# 78M05_RT9193.net
KiCad netlist of a schematic drawn in Altium Designer
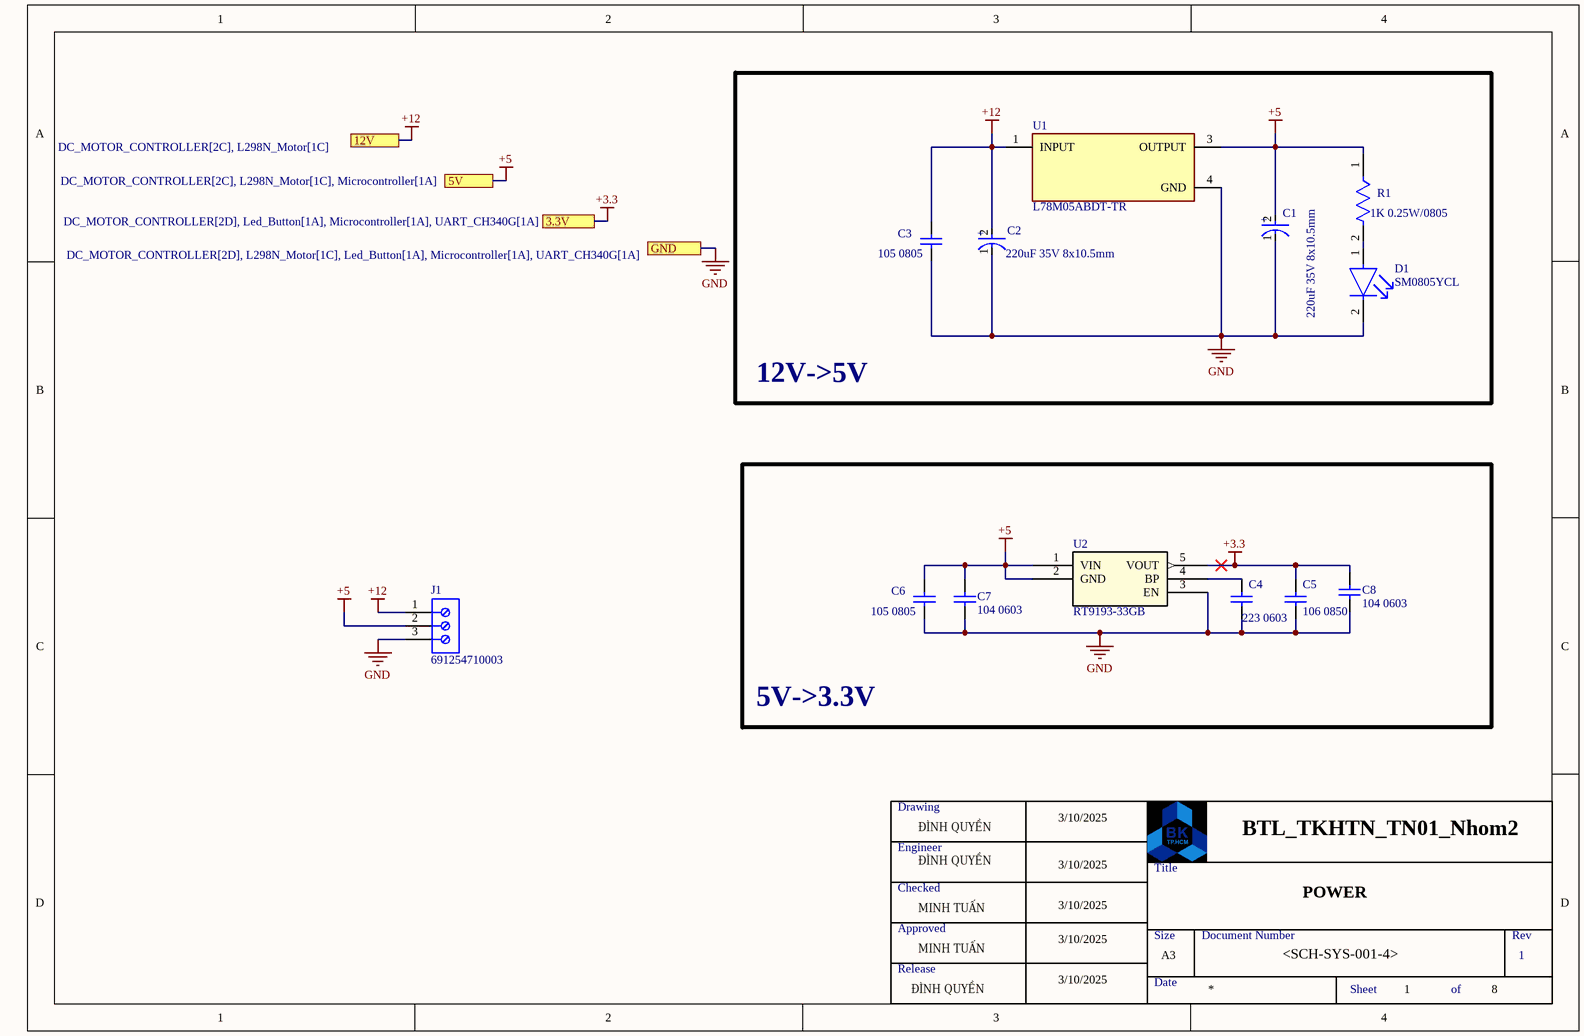
[diagram p0: 78M05_RT9193.SchDoc]

(export (version "E")
  (design (tool "Eeschema 10.0.6"))
  (components
    (comp (ref "C1")
      (value "220uF 35V 8x10.5mm")
      (footprint "FP-FPF-MFG")
      (description "CAP ALUM 220UF 20% 35V SMD")
      (fields (field (name "TOLERANCE") "20%") (field (name "VOLTAGE") "35V"))
      (libsource (lib "Altium Content Vault") (part "203bc49f2ac43e59fd269a8c329ed05"))
    )
    (comp (ref "C2")
      (value "220uF 35V 8x10.5mm")
      (footprint "FP-FPF-MFG")
      (description "CAP ALUM 220UF 20% 35V SMD")
      (fields (field (name "TOLERANCE") "20%") (field (name "VOLTAGE") "35V"))
      (libsource (lib "Altium Content Vault") (part "203bc49f2ac43e59fd269a8c329ed05"))
    )
    (comp (ref "C3")
      (value "105 0805")
      (footprint "CAPC0805(2012)145_M")
      (description "CAP 15nF 100V ±10% 0805 (2012 Metric) Thickness 1.45mm SMD")
      (fields (field (name "TOLERANCE") "Â±10%"))
      (libsource (lib "Altium Content Vault") (part "CAP"))
    )
    (comp (ref "C4")
      (value "223 0603")
      (footprint "CAPC1608X92X38ML15T08")
      (fields (field (name "MANUFACTURER") "Vitramon") (field (name "PART NUMBER") "VJ0603Y103JXXAC"))
      (libsource (lib "Altium Content Vault") (part "CAP"))
    )
    (comp (ref "C5")
      (value "106 0850")
      (footprint "CAPC0805(2012)145_M")
      (description "CAP 15nF 100V ±10% 0805 (2012 Metric) Thickness 1.45mm SMD")
      (fields (field (name "TOLERANCE") "Â±10%"))
      (libsource (lib "Altium Content Vault") (part "CAP"))
    )
    (comp (ref "C6")
      (value "105 0805")
      (footprint "CAPC0805(2012)145_M")
      (description "CAP 15nF 100V ±10% 0805 (2012 Metric) Thickness 1.45mm SMD")
      (fields (field (name "TOLERANCE") "Â±10%"))
      (libsource (lib "Altium Content Vault") (part "CAP"))
    )
    (comp (ref "C7")
      (value "104 0603")
      (footprint "CAPC1608X92X38ML15T08")
      (fields (field (name "MANUFACTURER") "Vitramon") (field (name "PART NUMBER") "VJ0603Y103JXXAC"))
      (libsource (lib "Altium Content Vault") (part "CAP"))
    )
    (comp (ref "C8")
      (value "104 0603")
      (footprint "CAPC1608X92X38ML15T08")
      (fields (field (name "MANUFACTURER") "Vitramon") (field (name "PART NUMBER") "VJ0603Y103JXXAC"))
      (libsource (lib "Altium Content Vault") (part "CAP"))
    )
    (comp (ref "D1")
      (value "SM0805YCL")
      (footprint "FP-SM0805YCL-MFG")
      (description "LED YELLOW CLEAR 0805 SMD")
      (libsource (lib "Altium Content Vault") (part "ab1c01a81903e929fc6c44469aada92"))
    )
    (comp (ref "J1")
      (value "691254710003")
      (footprint "691254710003")
      (libsource (lib "Altium Content Vault") (part "TBL - 1R - 03P - Screw"))
    )
    (comp (ref "R1")
      (value "1K 0.25W/0805")
      (footprint "FP-AF0805-IPC_C")
      (description "Anti-Sulfurated Chip Resistor Automotive Grade 75Ω 1% 0.125W ±100ppm/°C 0805")
      (fields (field (name "TOLERANCE") "1%"))
      (libsource (lib "Altium Content Vault") (part "1029c3af85768c4190bb7ad29bc67b5"))
    )
    (comp (ref "U1")
      (value "L78M05ABDT-TR")
      (footprint "FP-L78M05ABDT-TR-MFG")
      (description "IC REG LINEAR 5V 500MA DPAK")
      (fields (field (name "TOLERANCE") "4%"))
      (libsource (lib "Altium Content Vault") (part "9f44cecb34f7d82ec50de3d0489c717"))
    )
    (comp (ref "U2")
      (value "RT9193-33GB")
      (footprint "SOT-23-5_RIT")
      (description "No Description Available")
      (fields (field (name "COPYRIGHT") "Copyright (C) 2025 Ultra Librarian. All rights reserved."))
      (libsource (lib "RT9193-33GB") (part "RT9193-33GB"))
    )
  )
  (nets
    (net (code "1") (name "+3.3") (class "Default")
      (node (ref "C5") (pin "2") (pinfunction "2_2") (pintype "passive"))
      (node (ref "C8") (pin "2") (pinfunction "2_2") (pintype "passive"))
      (node (ref "U2") (pin "5") (pinfunction "VOUT_5") (pintype "output"))
    )
    (net (code "2") (name "+5") (class "Default")
      (node (ref "C1") (pin "2") (pinfunction "A_2") (pintype "passive"))
      (node (ref "C6") (pin "2") (pinfunction "2_2") (pintype "passive"))
      (node (ref "C7") (pin "2") (pinfunction "2_2") (pintype "passive"))
      (node (ref "J1") (pin "2") (pinfunction "2_2") (pintype "passive"))
      (node (ref "R1") (pin "1") (pinfunction "1_1") (pintype "passive"))
      (node (ref "U1") (pin "3") (pinfunction "OUTPUT_3") (pintype "power_in"))
      (node (ref "U2") (pin "1") (pinfunction "VIN_1") (pintype "power_in"))
      (node (ref "U2") (pin "2") (pinfunction "GND_2") (pintype "power_in"))
    )
    (net (code "3") (name "+12") (class "Default")
      (node (ref "C2") (pin "2") (pinfunction "A_2") (pintype "passive"))
      (node (ref "C3") (pin "2") (pinfunction "2_2") (pintype "passive"))
      (node (ref "J1") (pin "1") (pinfunction "1_1") (pintype "passive"))
      (node (ref "U1") (pin "1") (pinfunction "INPUT_1") (pintype "power_in"))
    )
    (net (code "4") (name "GND") (class "Default")
      (node (ref "C1") (pin "1") (pinfunction "C_1") (pintype "passive"))
      (node (ref "C2") (pin "1") (pinfunction "C_1") (pintype "passive"))
      (node (ref "C3") (pin "1") (pinfunction "1_1") (pintype "passive"))
      (node (ref "C4") (pin "1") (pinfunction "1_1") (pintype "passive"))
      (node (ref "C5") (pin "1") (pinfunction "1_1") (pintype "passive"))
      (node (ref "C6") (pin "1") (pinfunction "1_1") (pintype "passive"))
      (node (ref "C7") (pin "1") (pinfunction "1_1") (pintype "passive"))
      (node (ref "C8") (pin "1") (pinfunction "1_1") (pintype "passive"))
      (node (ref "D1") (pin "2") (pinfunction "C_2") (pintype "passive"))
      (node (ref "J1") (pin "3") (pinfunction "3_3") (pintype "passive"))
      (node (ref "U1") (pin "4") (pinfunction "GND_4") (pintype "power_in"))
      (node (ref "U2") (pin "3") (pinfunction "EN_3") (pintype "passive"))
    )
    (net (code "5") (name "Net-(D1-A)") (class "Default")
      (node (ref "D1") (pin "1") (pinfunction "A_1") (pintype "passive"))
      (node (ref "R1") (pin "2") (pinfunction "2_2") (pintype "passive"))
    )
    (net (code "6") (name "Net-(U2-BP)") (class "Default")
      (node (ref "C4") (pin "2") (pinfunction "2_2") (pintype "passive"))
      (node (ref "U2") (pin "4") (pinfunction "BP_4") (pintype "passive"))
    )
  )
)
